# PICSOIC8.net
KiCad netlist of a schematic drawn in EAGLE
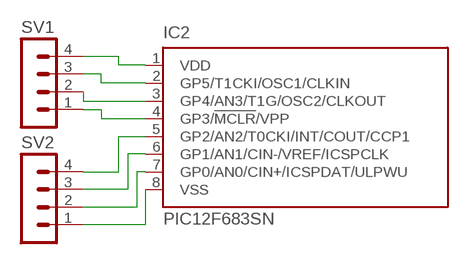
[diagram p0: schematic, sheet 1]

(export (version "E")
  (design (tool "Eeschema 10.0.6"))
  (components
    (comp (ref "IC2")
      (value "PIC12F683SN")
      (footprint "eagle-import:SO-08")
      (fields (field (name "MF") "MICROCHIP") (field (name "MPN") "PIC12F683-I/SN"))
      (libsource (lib "eagle-import") (part "PIC12F683SN"))
    )
    (comp (ref "SV1")
      (value "MA04-1")
      (footprint "eagle-import:MA04-1")
      (libsource (lib "eagle-import") (part "MA04-1"))
    )
    (comp (ref "SV2")
      (value "MA04-1")
      (footprint "eagle-import:MA04-1")
      (libsource (lib "eagle-import") (part "MA04-1"))
    )
  )
  (nets
    (net (code "1") (name "Net-(IC2-GP0{slash}AN0{slash}CIN+{slash}ICSPDAT{slash}ULPWU)") (class "Default")
      (node (ref "IC2") (pin "7") (pinfunction "GP0/AN0/CIN+/ICSPDAT/ULPWU_7") (pintype "bidirectional"))
      (node (ref "SV2") (pin "2") (pinfunction "2_2") (pintype "passive"))
    )
    (net (code "2") (name "Net-(IC2-GP1{slash}AN1{slash}CIN-{slash}VREF{slash}ICSPCLK)") (class "Default")
      (node (ref "IC2") (pin "6") (pinfunction "GP1/AN1/CIN-/VREF/ICSPCLK_6") (pintype "bidirectional"))
      (node (ref "SV2") (pin "3") (pinfunction "3_3") (pintype "passive"))
    )
    (net (code "3") (name "Net-(IC2-GP2{slash}AN2{slash}T0CKI{slash}INT{slash}COUT{slash}CCP1)") (class "Default")
      (node (ref "IC2") (pin "5") (pinfunction "GP2/AN2/T0CKI/INT/COUT/CCP1_5") (pintype "bidirectional"))
      (node (ref "SV2") (pin "4") (pinfunction "4_4") (pintype "passive"))
    )
    (net (code "4") (name "Net-(IC2-GP3{slash}~{MCLR}{slash}VPP)") (class "Default")
      (node (ref "IC2") (pin "4") (pinfunction "GP3/~{MCLR}/VPP_4") (pintype "bidirectional"))
      (node (ref "SV1") (pin "1") (pinfunction "1_1") (pintype "passive"))
    )
    (net (code "5") (name "Net-(IC2-GP4{slash}AN3{slash}T1G{slash}OSC2{slash}CLKOUT)") (class "Default")
      (node (ref "IC2") (pin "3") (pinfunction "GP4/AN3/T1G/OSC2/CLKOUT_3") (pintype "bidirectional"))
      (node (ref "SV1") (pin "2") (pinfunction "2_2") (pintype "passive"))
    )
    (net (code "6") (name "Net-(IC2-GP5{slash}T1CKI{slash}OSC1{slash}CLKIN)") (class "Default")
      (node (ref "IC2") (pin "2") (pinfunction "GP5/T1CKI/OSC1/CLKIN_2") (pintype "bidirectional"))
      (node (ref "SV1") (pin "3") (pinfunction "3_3") (pintype "passive"))
    )
    (net (code "7") (name "Net-(IC2-VDD)") (class "Default")
      (node (ref "IC2") (pin "1") (pinfunction "VDD_1") (pintype "power_in"))
      (node (ref "SV1") (pin "4") (pinfunction "4_4") (pintype "passive"))
    )
    (net (code "8") (name "Net-(IC2-VSS)") (class "Default")
      (node (ref "IC2") (pin "8") (pinfunction "VSS_8") (pintype "power_in"))
      (node (ref "SV2") (pin "1") (pinfunction "1_1") (pintype "passive"))
    )
  )
)
